# gyro.net
KiCad netlist of a schematic drawn in Altium Designer
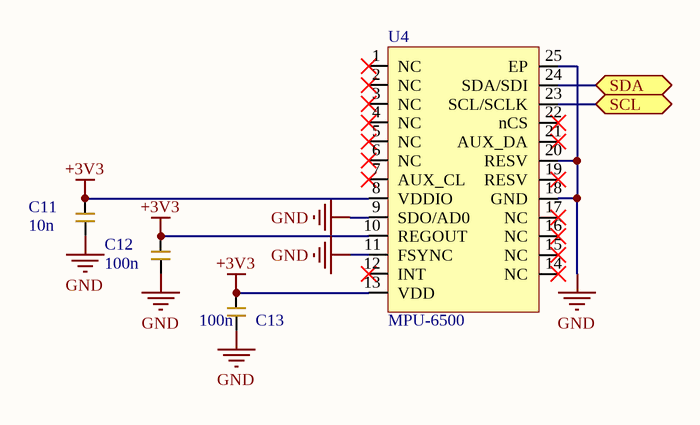
[diagram p0: gyro.SchDoc]

(export (version "E")
  (design (tool "Eeschema 10.0.6"))
  (components
    (comp (ref "C11")
      (value "10n")
      (footprint "CAP_0603")
      (description "Multilayer Ceramic Capacitors MLCC - SMD/SMT ROHS")
      (libsource (lib "Passive") (part "CAP_0603"))
    )
    (comp (ref "C12")
      (value "100n")
      (footprint "CAP_0603")
      (description "Multilayer Ceramic Capacitors MLCC - SMD/SMT ROHS")
      (libsource (lib "Passive") (part "CAP_0603"))
    )
    (comp (ref "C13")
      (value "100n")
      (footprint "CAP_0603")
      (description "Multilayer Ceramic Capacitors MLCC - SMD/SMT ROHS")
      (libsource (lib "Passive") (part "CAP_0603"))
    )
    (comp (ref "U4")
      (value "MPU-6500")
      (footprint "MPU-6500")
      (description "Accelerometer gyroscope QFN-24-EP(3x3) Accelerometers ROHS")
      (fields (field (name "MFR.") "TDK InvenSense"))
      (libsource (lib "ICs") (part "MPU-6500"))
    )
  )
  (nets
    (net (code "1") (name "+3V3") (class "Default")
      (node (ref "C11") (pin "2") (pintype "passive"))
      (node (ref "C12") (pin "2") (pintype "passive"))
      (node (ref "C13") (pin "2") (pintype "passive"))
      (node (ref "U4") (pin "10") (pinfunction "REGOUT_10") (pintype "passive"))
      (node (ref "U4") (pin "13") (pinfunction "VDD_13") (pintype "passive"))
      (node (ref "U4") (pin "8") (pinfunction "VDDIO_8") (pintype "passive"))
    )
    (net (code "2") (name "/SCL") (class "Default")
      (node (ref "U4") (pin "23") (pinfunction "SCL/SCLK_23") (pintype "passive"))
    )
    (net (code "3") (name "/SDA") (class "Default")
      (node (ref "U4") (pin "24") (pinfunction "SDA/SDI_24") (pintype "passive"))
    )
    (net (code "4") (name "GND") (class "Default")
      (node (ref "C11") (pin "1") (pintype "passive"))
      (node (ref "C12") (pin "1") (pintype "passive"))
      (node (ref "C13") (pin "1") (pintype "passive"))
      (node (ref "U4") (pin "11") (pinfunction "FSYNC_11") (pintype "passive"))
      (node (ref "U4") (pin "18") (pinfunction "GND_18") (pintype "passive"))
      (node (ref "U4") (pin "20") (pinfunction "RESV_20") (pintype "passive"))
      (node (ref "U4") (pin "25") (pinfunction "EP_25") (pintype "passive"))
      (node (ref "U4") (pin "9") (pinfunction "SDO/AD0_9") (pintype "passive"))
    )
    (net (code "5") (name "unconnected-(U4-AUX_CL-Pad7)") (class "Default")
      (node (ref "U4") (pin "7") (pinfunction "AUX_CL_7") (pintype "passive+no_connect"))
    )
    (net (code "6") (name "unconnected-(U4-AUX_DA-Pad21)") (class "Default")
      (node (ref "U4") (pin "21") (pinfunction "AUX_DA_21") (pintype "passive+no_connect"))
    )
    (net (code "7") (name "unconnected-(U4-INT-Pad12)") (class "Default")
      (node (ref "U4") (pin "12") (pinfunction "INT_12") (pintype "passive+no_connect"))
    )
    (net (code "8") (name "unconnected-(U4-NC-Pad1)") (class "Default")
      (node (ref "U4") (pin "1") (pinfunction "NC_1") (pintype "passive+no_connect"))
    )
    (net (code "9") (name "unconnected-(U4-NC-Pad2)") (class "Default")
      (node (ref "U4") (pin "2") (pinfunction "NC_2") (pintype "passive+no_connect"))
    )
    (net (code "10") (name "unconnected-(U4-NC-Pad3)") (class "Default")
      (node (ref "U4") (pin "3") (pinfunction "NC_3") (pintype "passive+no_connect"))
    )
    (net (code "11") (name "unconnected-(U4-NC-Pad4)") (class "Default")
      (node (ref "U4") (pin "4") (pinfunction "NC_4") (pintype "passive+no_connect"))
    )
    (net (code "12") (name "unconnected-(U4-NC-Pad5)") (class "Default")
      (node (ref "U4") (pin "5") (pinfunction "NC_5") (pintype "passive+no_connect"))
    )
    (net (code "13") (name "unconnected-(U4-NC-Pad6)") (class "Default")
      (node (ref "U4") (pin "6") (pinfunction "NC_6") (pintype "passive+no_connect"))
    )
    (net (code "14") (name "unconnected-(U4-NC-Pad14)") (class "Default")
      (node (ref "U4") (pin "14") (pinfunction "NC_14") (pintype "passive+no_connect"))
    )
    (net (code "15") (name "unconnected-(U4-NC-Pad15)") (class "Default")
      (node (ref "U4") (pin "15") (pinfunction "NC_15") (pintype "passive+no_connect"))
    )
    (net (code "16") (name "unconnected-(U4-NC-Pad16)") (class "Default")
      (node (ref "U4") (pin "16") (pinfunction "NC_16") (pintype "passive+no_connect"))
    )
    (net (code "17") (name "unconnected-(U4-NC-Pad17)") (class "Default")
      (node (ref "U4") (pin "17") (pinfunction "NC_17") (pintype "passive+no_connect"))
    )
    (net (code "18") (name "unconnected-(U4-RESV-Pad19)") (class "Default")
      (node (ref "U4") (pin "19") (pinfunction "RESV_19") (pintype "passive+no_connect"))
    )
    (net (code "19") (name "unconnected-(U4-nCS-Pad22)") (class "Default")
      (node (ref "U4") (pin "22") (pinfunction "nCS_22") (pintype "passive+no_connect"))
    )
  )
)
